# SparkFun_Pi_Wedge_B_Plus.net
KiCad netlist of a schematic drawn in EAGLE
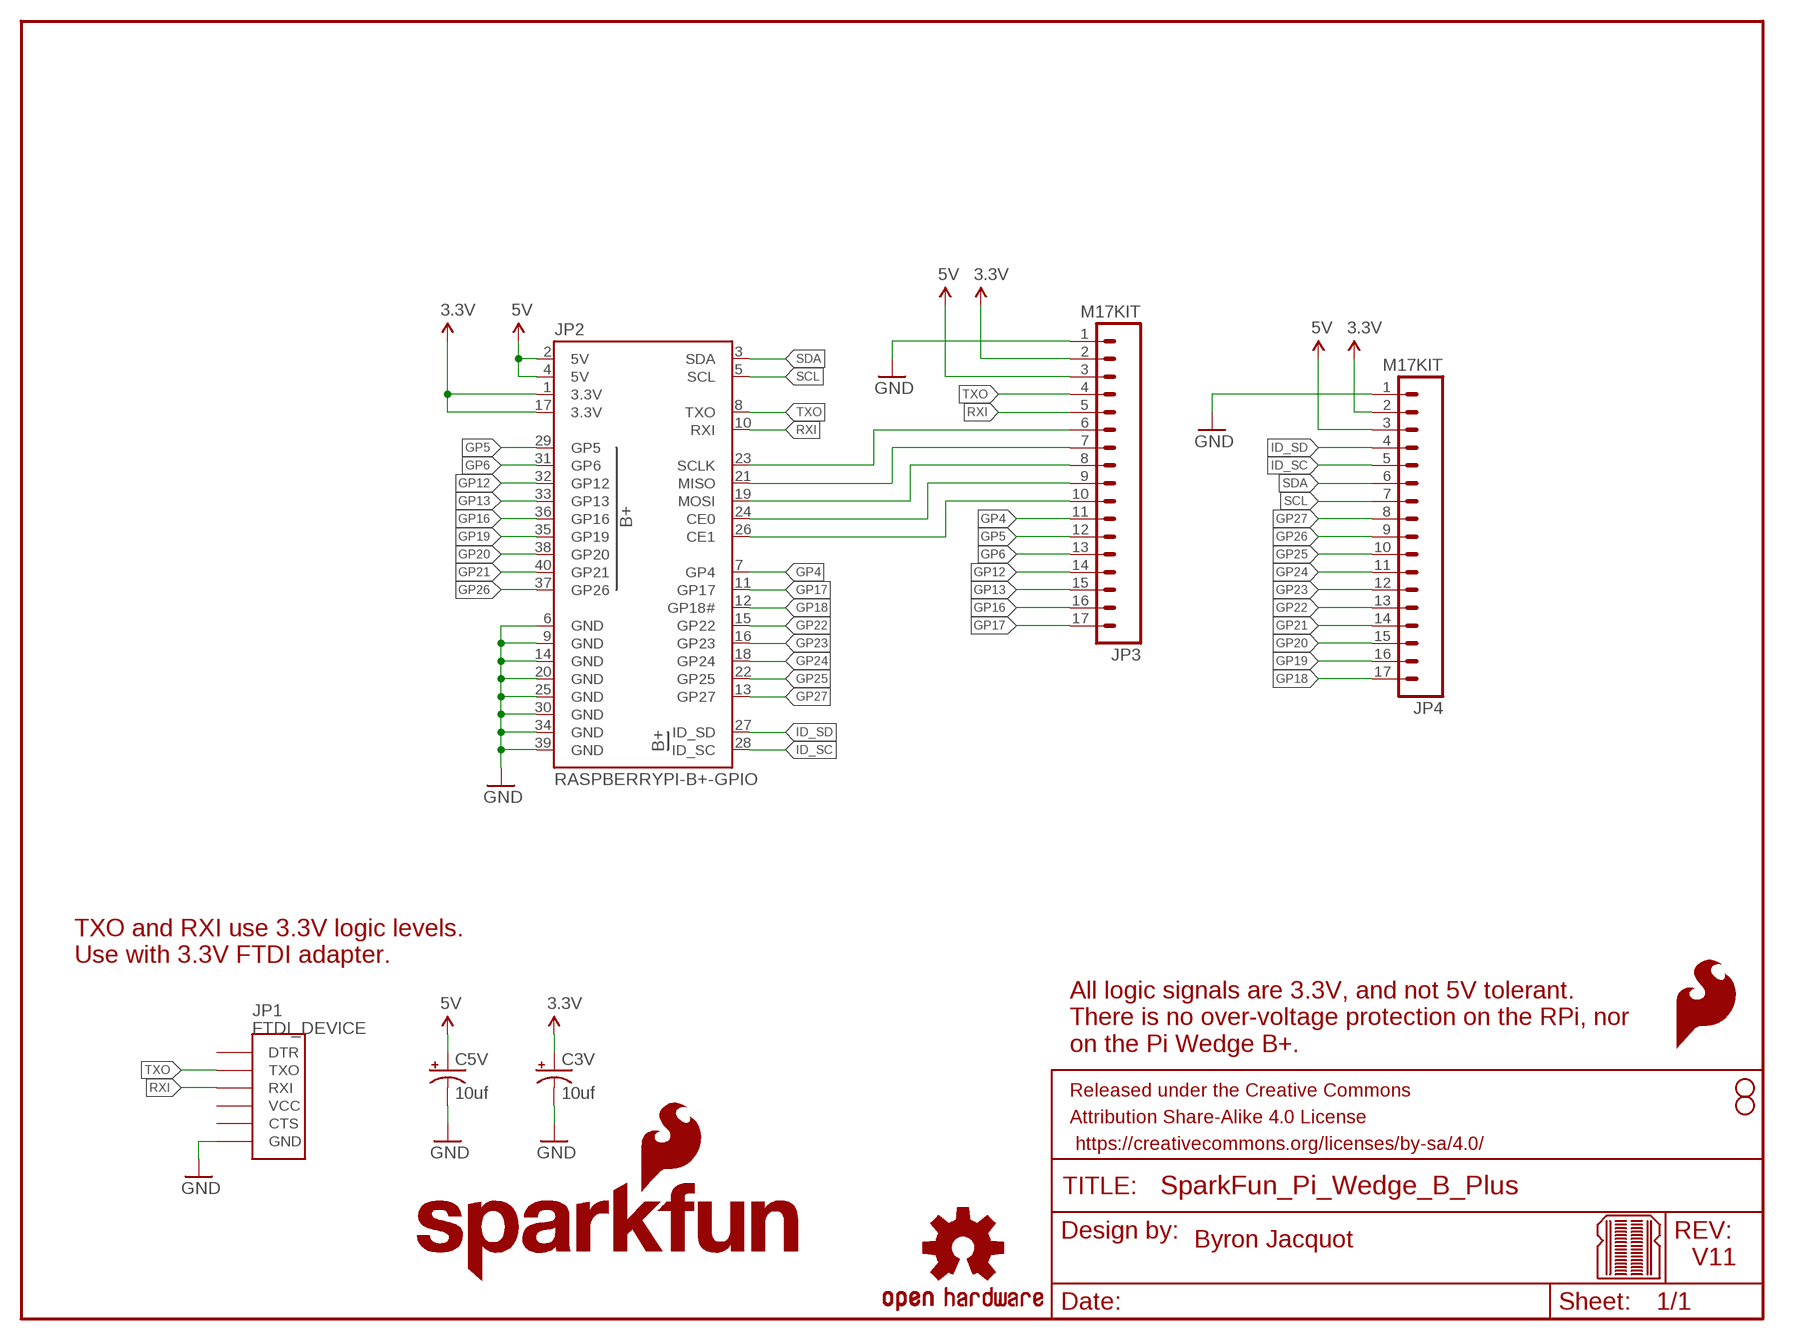
[diagram p0: schematic, sheet 1]

(export (version "E")
  (design (tool "Eeschema 10.0.6"))
  (components
    (comp (ref "C3V")
      (value "10uf")
      (footprint "eagle-import:CPOL-RADIAL-10UF-25V-KIT")
      (libsource (lib "eagle-import") (part "10UF-25V-20%(PTH)KIT"))
    )
    (comp (ref "C5V")
      (value "10uf")
      (footprint "eagle-import:CPOL-RADIAL-10UF-25V-KIT")
      (libsource (lib "eagle-import") (part "10UF-25V-20%(PTH)KIT"))
    )
    (comp (ref "FRAME2")
      (value "FRAME-LETTER")
      (footprint "eagle-import:CREATIVE_COMMONS")
      (libsource (lib "eagle-import") (part "FRAME-LETTER"))
    )
    (comp (ref "JP1")
      (value "FTDI_DEVICE")
      (footprint "eagle-import:FTDI_DEVICE_SIDE")
      (libsource (lib "eagle-import") (part "FTDI_DEVICE"))
    )
    (comp (ref "JP2")
      (value "RASPBERRYPI-B+-GPIO")
      (footprint "eagle-import:2X20-SHROUDED")
      (libsource (lib "eagle-import") (part "RASPBERRYPI-B+-GPIO"))
    )
    (comp (ref "JP3")
      (value "M17KIT")
      (footprint "eagle-import:1X17_NO_SILK_KIT")
      (libsource (lib "eagle-import") (part "M17KIT"))
    )
    (comp (ref "JP4")
      (value "M17KIT")
      (footprint "eagle-import:1X17_NO_SILK_KIT")
      (libsource (lib "eagle-import") (part "M17KIT"))
    )
    (comp (ref "LOGO1")
      (value "SFE_LOGO_NAME_FLAME.2_INCH")
      (footprint "eagle-import:SFE_LOGO_NAME_FLAME_.2")
      (libsource (lib "eagle-import") (part "SFE_LOGO_NAME_FLAME.2_INCH"))
    )
    (comp (ref "LOGO2")
      (value "SFE_LOGO_NAME_FLAME.2_INCH")
      (footprint "eagle-import:SFE_LOGO_NAME_FLAME_.2")
      (libsource (lib "eagle-import") (part "SFE_LOGO_NAME_FLAME.2_INCH"))
    )
    (comp (ref "LOGO3")
      (value "SFE_LOGO_FLAME.1_INCH")
      (footprint "eagle-import:SFE_LOGO_FLAME_.1")
      (libsource (lib "eagle-import") (part "SFE_LOGO_FLAME.1_INCH"))
    )
    (comp (ref "LOGO4")
      (value "SFE_LOGO_FLAME.1_INCH")
      (footprint "eagle-import:SFE_LOGO_FLAME_.1")
      (libsource (lib "eagle-import") (part "SFE_LOGO_FLAME.1_INCH"))
    )
    (comp (ref "LOGO5")
      (value "OSHW-LOGOS")
      (footprint "eagle-import:OSHW-LOGO-S")
      (libsource (lib "eagle-import") (part "OSHW-LOGOS"))
    )
    (comp (ref "STANDOFF1")
      (value "STAND-OFF")
      (footprint "eagle-import:STAND-OFF")
      (libsource (lib "eagle-import") (part "STAND-OFF"))
    )
    (comp (ref "STANDOFF2")
      (value "STAND-OFF")
      (footprint "eagle-import:STAND-OFF")
      (libsource (lib "eagle-import") (part "STAND-OFF"))
    )
    (comp (ref "U$2")
      (value "BREADBOARD_PATTERN")
      (footprint "eagle-import:BREADBOARD_SPACING")
      (libsource (lib "eagle-import") (part "BREADBOARD_PATTERN"))
    )
  )
  (nets
    (net (code "1") (name "3.3V") (class "Default")
      (node (ref "C3V") (pin "1") (pinfunction "+_1") (pintype "passive"))
      (node (ref "JP2") (pin "1") (pinfunction "3.3V_1") (pintype "power_in"))
      (node (ref "JP2") (pin "17") (pinfunction "3.3V_17") (pintype "power_in"))
      (node (ref "JP3") (pin "2") (pinfunction "2_2") (pintype "passive"))
      (node (ref "JP4") (pin "2") (pinfunction "2_2") (pintype "passive"))
    )
    (net (code "2") (name "5V") (class "Default")
      (node (ref "C5V") (pin "1") (pinfunction "+_1") (pintype "passive"))
      (node (ref "JP2") (pin "2") (pinfunction "5V_2") (pintype "power_in"))
      (node (ref "JP2") (pin "4") (pinfunction "5V_4") (pintype "power_in"))
      (node (ref "JP3") (pin "3") (pinfunction "3_3") (pintype "passive"))
      (node (ref "JP4") (pin "3") (pinfunction "3_3") (pintype "passive"))
    )
    (net (code "3") (name "GND") (class "Default")
      (node (ref "C3V") (pin "2") (pinfunction "-_2") (pintype "passive"))
      (node (ref "C5V") (pin "2") (pinfunction "-_2") (pintype "passive"))
      (node (ref "JP1") (pin "P$6") (pinfunction "GND_P$6") (pintype "bidirectional"))
      (node (ref "JP2") (pin "14") (pinfunction "GND_14") (pintype "power_in"))
      (node (ref "JP2") (pin "20") (pinfunction "GND_20") (pintype "power_in"))
      (node (ref "JP2") (pin "25") (pinfunction "GND_25") (pintype "power_in"))
      (node (ref "JP2") (pin "30") (pinfunction "GND_30") (pintype "power_in"))
      (node (ref "JP2") (pin "34") (pinfunction "GND_34") (pintype "power_in"))
      (node (ref "JP2") (pin "39") (pinfunction "GND_39") (pintype "power_in"))
      (node (ref "JP2") (pin "6") (pinfunction "GND_6") (pintype "power_in"))
      (node (ref "JP2") (pin "9") (pinfunction "GND_9") (pintype "power_in"))
      (node (ref "JP3") (pin "1") (pinfunction "1_1") (pintype "passive"))
      (node (ref "JP4") (pin "1") (pinfunction "1_1") (pintype "passive"))
    )
    (net (code "4") (name "GP4") (class "Default")
      (node (ref "JP2") (pin "7") (pinfunction "GP4_7") (pintype "bidirectional"))
      (node (ref "JP3") (pin "11") (pinfunction "11_11") (pintype "passive"))
    )
    (net (code "5") (name "GP5") (class "Default")
      (node (ref "JP2") (pin "29") (pinfunction "GP5_29") (pintype "bidirectional"))
      (node (ref "JP3") (pin "12") (pinfunction "12_12") (pintype "passive"))
    )
    (net (code "6") (name "GP6") (class "Default")
      (node (ref "JP2") (pin "31") (pinfunction "GP6_31") (pintype "bidirectional"))
      (node (ref "JP3") (pin "13") (pinfunction "13_13") (pintype "passive"))
    )
    (net (code "7") (name "GP12") (class "Default")
      (node (ref "JP2") (pin "32") (pinfunction "GP12_32") (pintype "bidirectional"))
      (node (ref "JP3") (pin "14") (pinfunction "14_14") (pintype "passive"))
    )
    (net (code "8") (name "GP13") (class "Default")
      (node (ref "JP2") (pin "33") (pinfunction "GP13_33") (pintype "bidirectional"))
      (node (ref "JP3") (pin "15") (pinfunction "15_15") (pintype "passive"))
    )
    (net (code "9") (name "GP16") (class "Default")
      (node (ref "JP2") (pin "36") (pinfunction "GP16_36") (pintype "bidirectional"))
      (node (ref "JP3") (pin "16") (pinfunction "16_16") (pintype "passive"))
    )
    (net (code "10") (name "GP17") (class "Default")
      (node (ref "JP2") (pin "11") (pinfunction "GP17_11") (pintype "bidirectional"))
      (node (ref "JP3") (pin "17") (pinfunction "17_17") (pintype "passive"))
    )
    (net (code "11") (name "GP18") (class "Default")
      (node (ref "JP2") (pin "12") (pinfunction "GP18#_12") (pintype "bidirectional"))
      (node (ref "JP4") (pin "17") (pinfunction "17_17") (pintype "passive"))
    )
    (net (code "12") (name "GP19") (class "Default")
      (node (ref "JP2") (pin "35") (pinfunction "GP19_35") (pintype "bidirectional"))
      (node (ref "JP4") (pin "16") (pinfunction "16_16") (pintype "passive"))
    )
    (net (code "13") (name "GP20") (class "Default")
      (node (ref "JP2") (pin "38") (pinfunction "GP20_38") (pintype "bidirectional"))
      (node (ref "JP4") (pin "15") (pinfunction "15_15") (pintype "passive"))
    )
    (net (code "14") (name "GP21") (class "Default")
      (node (ref "JP2") (pin "40") (pinfunction "GP21_40") (pintype "bidirectional"))
      (node (ref "JP4") (pin "14") (pinfunction "14_14") (pintype "passive"))
    )
    (net (code "15") (name "GP22") (class "Default")
      (node (ref "JP2") (pin "15") (pinfunction "GP22_15") (pintype "bidirectional"))
      (node (ref "JP4") (pin "13") (pinfunction "13_13") (pintype "passive"))
    )
    (net (code "16") (name "GP23") (class "Default")
      (node (ref "JP2") (pin "16") (pinfunction "GP23_16") (pintype "bidirectional"))
      (node (ref "JP4") (pin "12") (pinfunction "12_12") (pintype "passive"))
    )
    (net (code "17") (name "GP24") (class "Default")
      (node (ref "JP2") (pin "18") (pinfunction "GP24_18") (pintype "bidirectional"))
      (node (ref "JP4") (pin "11") (pinfunction "11_11") (pintype "passive"))
    )
    (net (code "18") (name "GP25") (class "Default")
      (node (ref "JP2") (pin "22") (pinfunction "GP25_22") (pintype "bidirectional"))
      (node (ref "JP4") (pin "10") (pinfunction "10_10") (pintype "passive"))
    )
    (net (code "19") (name "GP26") (class "Default")
      (node (ref "JP2") (pin "37") (pinfunction "GP26_37") (pintype "bidirectional"))
      (node (ref "JP4") (pin "9") (pinfunction "9_9") (pintype "passive"))
    )
    (net (code "20") (name "GP27") (class "Default")
      (node (ref "JP2") (pin "13") (pinfunction "GP27_13") (pintype "bidirectional"))
      (node (ref "JP4") (pin "8") (pinfunction "8_8") (pintype "passive"))
    )
    (net (code "21") (name "ID_SC") (class "Default")
      (node (ref "JP2") (pin "28") (pinfunction "ID_SC_28") (pintype "bidirectional"))
      (node (ref "JP4") (pin "5") (pinfunction "5_5") (pintype "passive"))
    )
    (net (code "22") (name "ID_SD") (class "Default")
      (node (ref "JP2") (pin "27") (pinfunction "ID_SD_27") (pintype "bidirectional"))
      (node (ref "JP4") (pin "4") (pinfunction "4_4") (pintype "passive"))
    )
    (net (code "23") (name "Net-(JP2-CE0)") (class "Default")
      (node (ref "JP2") (pin "24") (pinfunction "CE0_24") (pintype "output"))
      (node (ref "JP3") (pin "9") (pinfunction "9_9") (pintype "passive"))
    )
    (net (code "24") (name "Net-(JP2-CE1)") (class "Default")
      (node (ref "JP2") (pin "26") (pinfunction "CE1_26") (pintype "output"))
      (node (ref "JP3") (pin "10") (pinfunction "10_10") (pintype "passive"))
    )
    (net (code "25") (name "Net-(JP2-MISO)") (class "Default")
      (node (ref "JP2") (pin "21") (pinfunction "MISO_21") (pintype "input"))
      (node (ref "JP3") (pin "7") (pinfunction "7_7") (pintype "passive"))
    )
    (net (code "26") (name "Net-(JP2-MOSI)") (class "Default")
      (node (ref "JP2") (pin "19") (pinfunction "MOSI_19") (pintype "output"))
      (node (ref "JP3") (pin "8") (pinfunction "8_8") (pintype "passive"))
    )
    (net (code "27") (name "Net-(JP2-SCLK)") (class "Default")
      (node (ref "JP2") (pin "23") (pinfunction "SCLK_23") (pintype "output"))
      (node (ref "JP3") (pin "6") (pinfunction "6_6") (pintype "passive"))
    )
    (net (code "28") (name "RXI") (class "Default")
      (node (ref "JP1") (pin "P$3") (pinfunction "RXI_P$3") (pintype "bidirectional"))
      (node (ref "JP2") (pin "10") (pinfunction "RXI_10") (pintype "input"))
      (node (ref "JP3") (pin "5") (pinfunction "5_5") (pintype "passive"))
    )
    (net (code "29") (name "SCL") (class "Default")
      (node (ref "JP2") (pin "5") (pinfunction "SCL_5") (pintype "bidirectional"))
      (node (ref "JP4") (pin "7") (pinfunction "7_7") (pintype "passive"))
    )
    (net (code "30") (name "SDA") (class "Default")
      (node (ref "JP2") (pin "3") (pinfunction "SDA_3") (pintype "bidirectional"))
      (node (ref "JP4") (pin "6") (pinfunction "6_6") (pintype "passive"))
    )
    (net (code "31") (name "TXO") (class "Default")
      (node (ref "JP1") (pin "P$2") (pinfunction "TXO_P$2") (pintype "bidirectional"))
      (node (ref "JP2") (pin "8") (pinfunction "TXO_8") (pintype "output"))
      (node (ref "JP3") (pin "4") (pinfunction "4_4") (pintype "passive"))
    )
    (net (code "32") (name "unconnected-(JP1-CTS-PadP$5)") (class "Default")
      (node (ref "JP1") (pin "P$5") (pinfunction "CTS_P$5") (pintype "bidirectional"))
    )
    (net (code "33") (name "unconnected-(JP1-DTR-PadP$1)") (class "Default")
      (node (ref "JP1") (pin "P$1") (pinfunction "DTR_P$1") (pintype "bidirectional"))
    )
    (net (code "34") (name "unconnected-(JP1-VCC-PadP$4)") (class "Default")
      (node (ref "JP1") (pin "P$4") (pinfunction "VCC_P$4") (pintype "bidirectional"))
    )
  )
)
